# XWQ_Board1.net
KiCad netlist of a schematic drawn in EasyEDA Pro
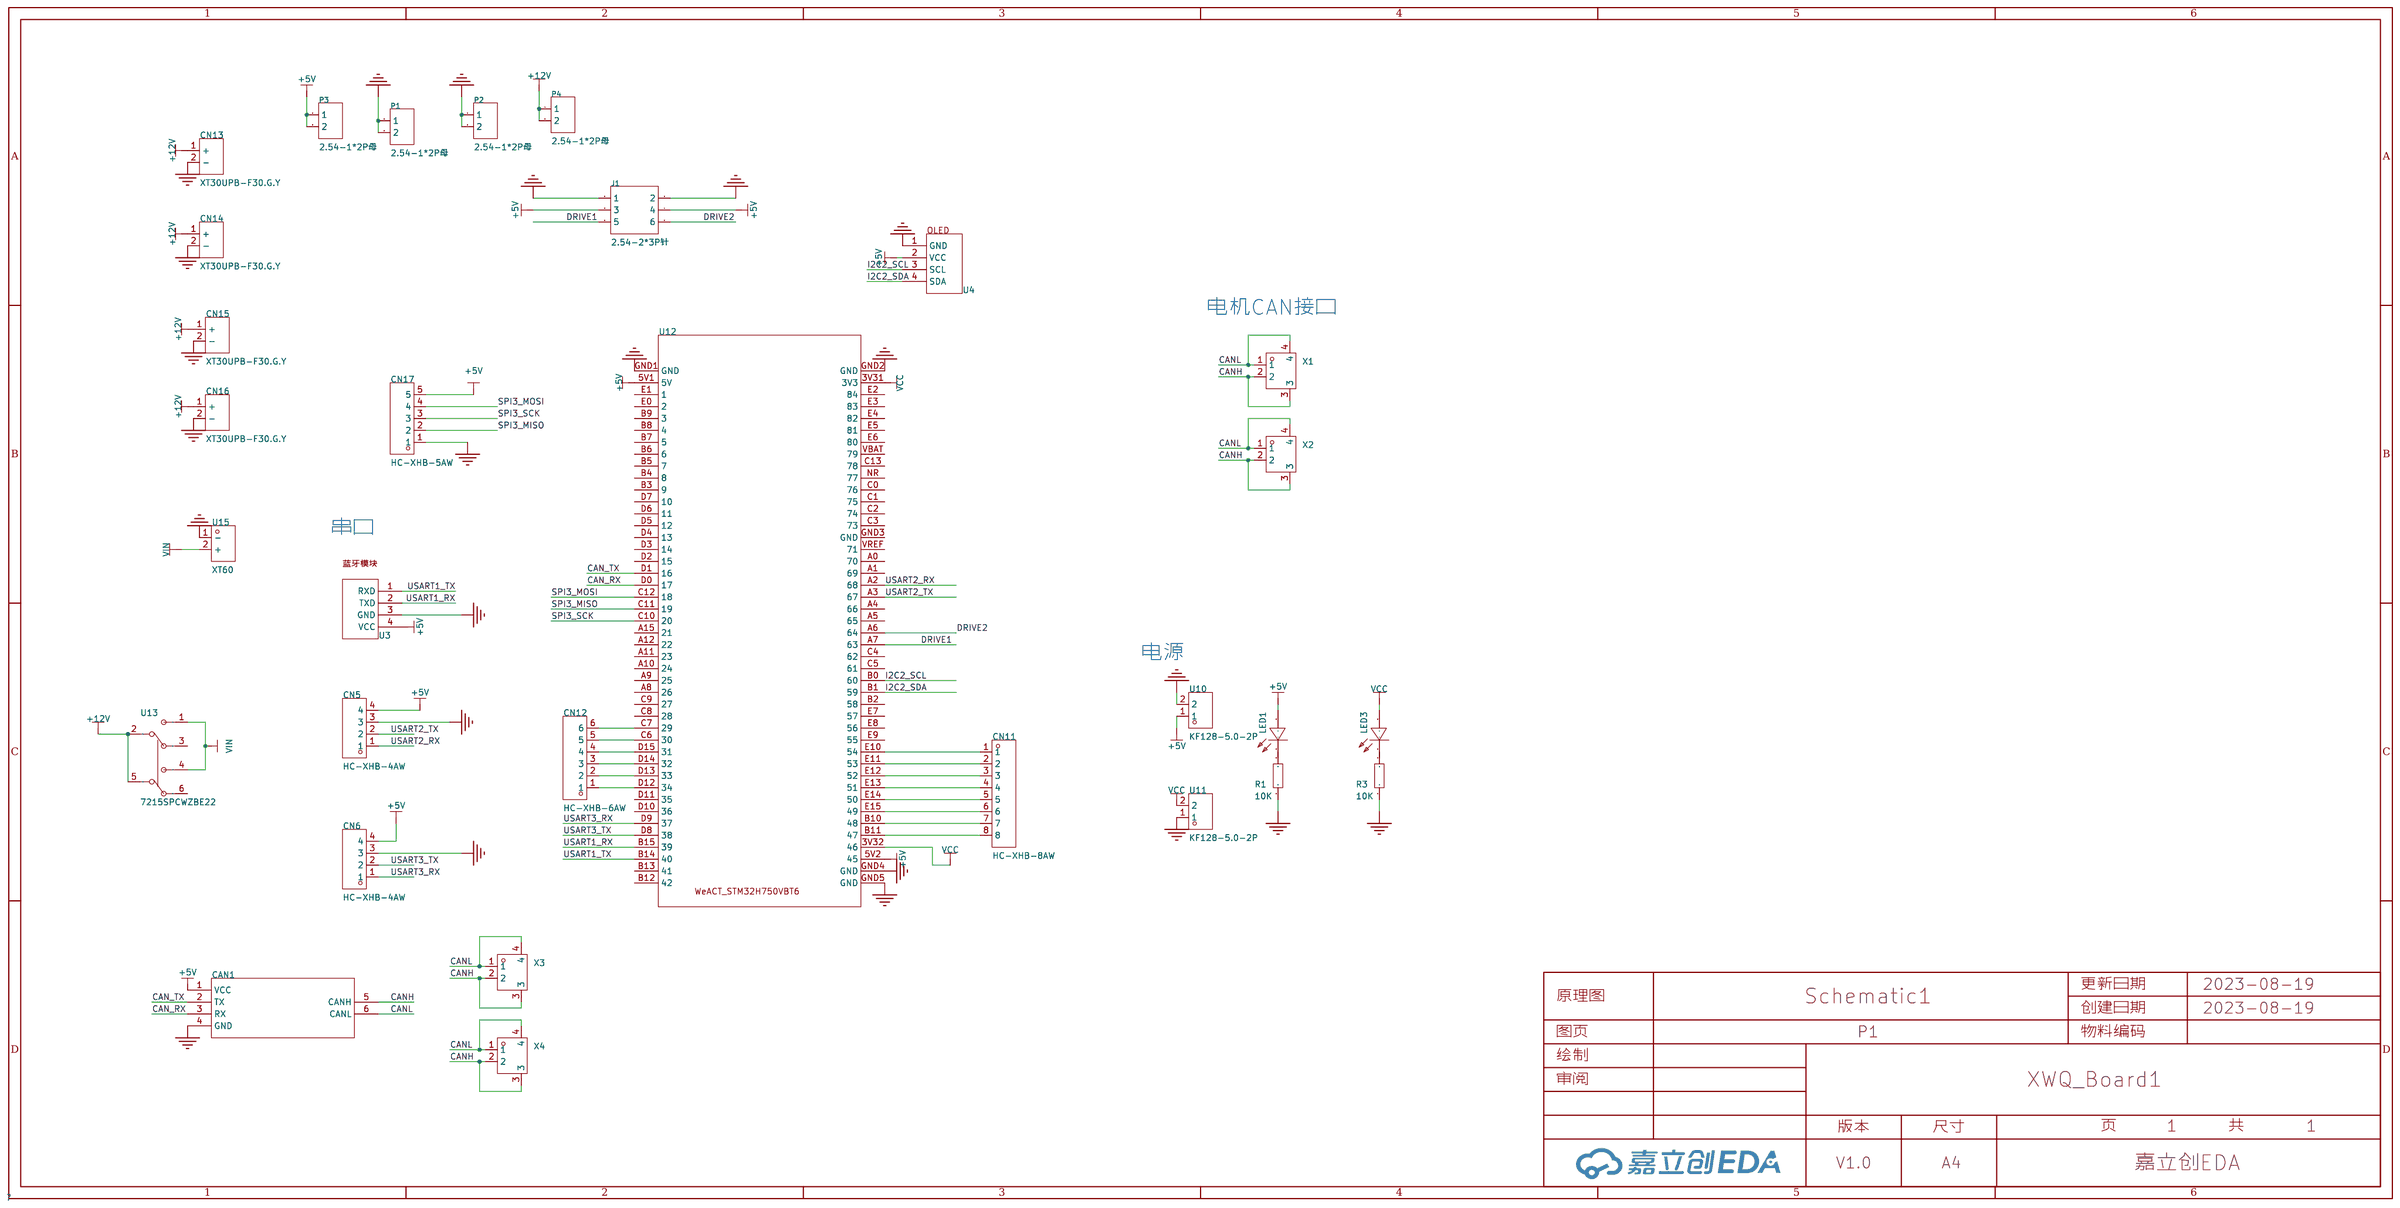
[diagram p0: schematic sheet]

(export (version "E")
  (design (tool "Eeschema 10.0.6"))
  (components
    (comp (ref "CAN1")
      (value "~")
      (footprint "easyedapro:CAN模块")
      (libsource (lib "easyedapro") (part "CAN模块"))
    )
    (comp (ref "CN5")
      (value "HC-XHB-4AW")
      (footprint "easyedapro:CONN-TH_4P-P2.5_HCTL_HC-XHB-4AW")
      (description "参考系列:-;间距:2.5mm;插针结构:1x4P;排数:1;每排PIN数:4;行距:-;公母:公型插针;安装方式:弯插;额定电流:3A;工作温度范围:-25°C~+85°C;")
      (fields (field (name "Manufacturer") "HCTL(华灿天禄)"))
      (libsource (lib "easyedapro") (part "HC-XHB-4AW"))
    )
    (comp (ref "CN6")
      (value "HC-XHB-4AW")
      (footprint "easyedapro:CONN-TH_4P-P2.5_HCTL_HC-XHB-4AW")
      (description "参考系列:-;间距:2.5mm;插针结构:1x4P;排数:1;每排PIN数:4;行距:-;公母:公型插针;安装方式:弯插;额定电流:3A;工作温度范围:-25°C~+85°C;")
      (fields (field (name "Manufacturer") "HCTL(华灿天禄)"))
      (libsource (lib "easyedapro") (part "HC-XHB-4AW"))
    )
    (comp (ref "CN11")
      (value "HC-XHB-8AW")
      (footprint "easyedapro:CONN-TH_HC-XHB-8AW")
      (description "参考系列:-;间距:2.5mm;插针结构:1x8P;排数:1;每排PIN数:8;行距:-;公母:公型插针;安装方式:弯插;额定电流:3A;工作温度范围:-25°C~+85°C;")
      (fields (field (name "Manufacturer") "HCTL(华灿天禄)"))
      (libsource (lib "easyedapro") (part "HC-XHB-8AW"))
    )
    (comp (ref "CN12")
      (value "HC-XHB-6AW")
      (footprint "easyedapro:CONN-TH_6P-P2.50_HCTL_HC-XHB-6AW")
      (description "参考系列:-;间距:2.5mm;插针结构:1x6P;排数:1;每排PIN数:6;行距:-;公母:公型插针;安装方式:弯插;额定电流:3A;工作温度范围:-25°C~+85°C;")
      (fields (field (name "Manufacturer") "HCTL(华灿天禄)"))
      (libsource (lib "easyedapro") (part "HC-XHB-6AW"))
    )
    (comp (ref "CN13")
      (value "XT30UPB-F30.G.Y")
      (footprint "easyedapro:CONN-TH_XT30UPB-F")
      (description "模型插头连接器")
      (fields (field (name "Manufacturer") "AMASS(艾迈斯)"))
      (libsource (lib "easyedapro") (part "XT30UPB-F"))
    )
    (comp (ref "CN14")
      (value "XT30UPB-F30.G.Y")
      (footprint "easyedapro:CONN-TH_XT30UPB-F")
      (description "模型插头连接器")
      (fields (field (name "Manufacturer") "AMASS(艾迈斯)"))
      (libsource (lib "easyedapro") (part "XT30UPB-F"))
    )
    (comp (ref "CN15")
      (value "XT30UPB-F30.G.Y")
      (footprint "easyedapro:CONN-TH_XT30UPB-F")
      (description "模型插头连接器")
      (fields (field (name "Manufacturer") "AMASS(艾迈斯)"))
      (libsource (lib "easyedapro") (part "XT30UPB-F"))
    )
    (comp (ref "CN16")
      (value "XT30UPB-F30.G.Y")
      (footprint "easyedapro:CONN-TH_XT30UPB-F")
      (description "模型插头连接器")
      (fields (field (name "Manufacturer") "AMASS(艾迈斯)"))
      (libsource (lib "easyedapro") (part "XT30UPB-F"))
    )
    (comp (ref "CN17")
      (value "HC-XHB-5AW")
      (footprint "easyedapro:CONN-TH_5P-P2.50_HCTL_HC-XHB-5AW")
      (description "参考系列:-;间距:2.5mm;插针结构:1x5P;排数:1;每排PIN数:5;行距:-;公母:公型插针;安装方式:弯插;额定电流:3A;工作温度范围:-25°C~+85°C;")
      (fields (field (name "Manufacturer") "HCTL(华灿天禄)"))
      (libsource (lib "easyedapro") (part "HC-XHB-5AW"))
    )
    (comp (ref "J1")
      (value "2.54-2*3P针")
      (footprint "easyedapro:HDR-TH_6P-P2.54-V-M-R2-C3-S2.54-1")
      (fields (field (name "Manufacturer") "BOOMELE(博穆精密)"))
      (libsource (lib "easyedapro") (part "Header-Male-2.54_2x3"))
    )
    (comp (ref "LED1")
      (value "NCD0805R1")
      (footprint "easyedapro:LED0805-RD_RED")
      (description "发光颜色:红灯;")
      (fields (field (name "Manufacturer") "国星光电"))
      (libsource (lib "easyedapro") (part "FC-2012HRK-620D"))
    )
    (comp (ref "LED3")
      (value "NCD0805R1")
      (footprint "easyedapro:LED0805-RD_RED")
      (description "发光颜色:红灯;")
      (fields (field (name "Manufacturer") "国星光电"))
      (libsource (lib "easyedapro") (part "FC-2012HRK-620D"))
    )
    (comp (ref "P1")
      (value "2.54-1*2P母")
      (footprint "easyedapro:HDR-TH_2P-P2.54-V-F")
      (description "排数:单排;总孔位数:2;间距:2.54mm;插孔结构:1x2P;行距:-;安装类型:直插;塑高:-;触头材质:-;触头镀层:-;")
      (fields (field (name "Manufacturer") "BOOMELE(博穆精密)"))
      (libsource (lib "easyedapro") (part "Header-Female-2.54_1x2"))
    )
    (comp (ref "P2")
      (value "2.54-1*2P母")
      (footprint "easyedapro:HDR-TH_2P-P2.54-V-F")
      (description "排数:单排;总孔位数:2;间距:2.54mm;插孔结构:1x2P;行距:-;安装类型:直插;塑高:-;触头材质:-;触头镀层:-;")
      (fields (field (name "Manufacturer") "BOOMELE(博穆精密)"))
      (libsource (lib "easyedapro") (part "Header-Female-2.54_1x2"))
    )
    (comp (ref "P3")
      (value "2.54-1*2P母")
      (footprint "easyedapro:HDR-TH_2P-P2.54-V-F")
      (description "排数:单排;总孔位数:2;间距:2.54mm;插孔结构:1x2P;行距:-;安装类型:直插;塑高:-;触头材质:-;触头镀层:-;")
      (fields (field (name "Manufacturer") "BOOMELE(博穆精密)"))
      (libsource (lib "easyedapro") (part "Header-Female-2.54_1x2"))
    )
    (comp (ref "P4")
      (value "2.54-1*2P母")
      (footprint "easyedapro:HDR-TH_2P-P2.54-V-F")
      (description "排数:单排;总孔位数:2;间距:2.54mm;插孔结构:1x2P;行距:-;安装类型:直插;塑高:-;触头材质:-;触头镀层:-;")
      (fields (field (name "Manufacturer") "BOOMELE(博穆精密)"))
      (libsource (lib "easyedapro") (part "Header-Female-2.54_1x2"))
    )
    (comp (ref "R1") (value "10K") (footprint "easyedapro:R0603") (libsource (lib "easyedapro") (part "电阻")))
    (comp (ref "R3") (value "10K") (footprint "easyedapro:R0603") (libsource (lib "easyedapro") (part "电阻")))
    (comp (ref "U3") (value "~") (footprint "easyedapro:蓝牙模块") (libsource (lib "easyedapro") (part "蓝牙模块")))
    (comp (ref "U4") (value "~") (footprint "easyedapro:OLED") (libsource (lib "easyedapro") (part "OLED")))
    (comp (ref "U10")
      (value "KF128-5.0-2P")
      (footprint "easyedapro:CONN-TH_P5.00_KF128-5.0-2P")
      (fields (field (name "Manufacturer") "KEFA(科发)"))
      (libsource (lib "easyedapro") (part "KF128-5.0-2P"))
    )
    (comp (ref "U11")
      (value "KF128-5.0-2P")
      (footprint "easyedapro:CONN-TH_P5.00_KF128-5.0-2P")
      (fields (field (name "Manufacturer") "KEFA(科发)"))
      (libsource (lib "easyedapro") (part "KF128-5.0-2P"))
    )
    (comp (ref "U12")
      (value "~")
      (footprint "easyedapro:WeAct_STM32H750VBT6核心板")
      (libsource (lib "easyedapro") (part "STM32H750VBT6"))
    )
    (comp (ref "U13")
      (value "7215SPCWZBE22")
      (footprint "easyedapro:SW-TH_6P-L12.7-W11.4-P4.70-LS4.8")
      (fields (field (name "Manufacturer") "CK"))
      (libsource (lib "easyedapro") (part "7215SPCWZBE22"))
    )
    (comp (ref "U15")
      (value "XT60")
      (footprint "easyedapro:CONN-TH_XT60")
      (description "模型锂电连接器 XT60-M")
      (fields (field (name "Manufacturer") "AMASS(艾迈斯)"))
      (libsource (lib "easyedapro") (part "XT60"))
    )
    (comp (ref "X1")
      (value "GH125-S02DCA-00")
      (footprint "easyedapro:CONN-SMD_2P-P1.25_JUSHUO_GH125-S02DCA-00")
      (description "参考系列:-;间距:1.25mm;插针结构:1x2P;排数:1;每排PIN数:2;行距:-;公母:公型插针;安装方式:卧贴;额定电流:1A;工作温度范围:-25°C~+85°C;")
      (fields (field (name "Manufacturer") "JS(钜硕电子)"))
      (libsource (lib "easyedapro") (part "GH125-S02DCA-00"))
    )
    (comp (ref "X2")
      (value "GH125-S02DCA-00")
      (footprint "easyedapro:CONN-SMD_2P-P1.25_JUSHUO_GH125-S02DCA-00")
      (description "参考系列:-;间距:1.25mm;插针结构:1x2P;排数:1;每排PIN数:2;行距:-;公母:公型插针;安装方式:卧贴;额定电流:1A;工作温度范围:-25°C~+85°C;")
      (fields (field (name "Manufacturer") "JS(钜硕电子)"))
      (libsource (lib "easyedapro") (part "GH125-S02DCA-00"))
    )
    (comp (ref "X3")
      (value "GH125-S02DCA-00")
      (footprint "easyedapro:CONN-SMD_2P-P1.25_JUSHUO_GH125-S02DCA-00")
      (description "参考系列:-;间距:1.25mm;插针结构:1x2P;排数:1;每排PIN数:2;行距:-;公母:公型插针;安装方式:卧贴;额定电流:1A;工作温度范围:-25°C~+85°C;")
      (fields (field (name "Manufacturer") "JS(钜硕电子)"))
      (libsource (lib "easyedapro") (part "GH125-S02DCA-00"))
    )
    (comp (ref "X4")
      (value "GH125-S02DCA-00")
      (footprint "easyedapro:CONN-SMD_2P-P1.25_JUSHUO_GH125-S02DCA-00")
      (description "参考系列:-;间距:1.25mm;插针结构:1x2P;排数:1;每排PIN数:2;行距:-;公母:公型插针;安装方式:卧贴;额定电流:1A;工作温度范围:-25°C~+85°C;")
      (fields (field (name "Manufacturer") "JS(钜硕电子)"))
      (libsource (lib "easyedapro") (part "GH125-S02DCA-00"))
    )
  )
  (nets
    (net (code "1") (name "+5V") (class "Default")
      (node (ref "CAN1") (pin "1") (pinfunction "VCC_1") (pintype "input"))
      (node (ref "CN17") (pin "5") (pinfunction "5_5") (pintype "input"))
      (node (ref "CN5") (pin "4") (pinfunction "4_4") (pintype "input"))
      (node (ref "CN6") (pin "4") (pinfunction "4_4") (pintype "input"))
      (node (ref "J1") (pin "3") (pinfunction "3_3") (pintype "input"))
      (node (ref "J1") (pin "4") (pinfunction "4_4") (pintype "input"))
      (node (ref "LED1") (pin "2") (pinfunction "+_2") (pintype "input"))
      (node (ref "P3") (pin "1") (pinfunction "1_1") (pintype "input"))
      (node (ref "P3") (pin "2") (pinfunction "2_2") (pintype "input"))
      (node (ref "U10") (pin "1") (pinfunction "1_1") (pintype "input"))
      (node (ref "U12") (pin "5V1") (pinfunction "5V_5V1") (pintype "input"))
      (node (ref "U12") (pin "5V2") (pinfunction "45_5V2") (pintype "input"))
      (node (ref "U3") (pin "4") (pinfunction "VCC_4") (pintype "input"))
      (node (ref "U4") (pin "2") (pinfunction "VCC_2") (pintype "input"))
    )
    (net (code "2") (name "+12V") (class "Default")
      (node (ref "CN13") (pin "1") (pinfunction "+_1") (pintype "input"))
      (node (ref "CN14") (pin "1") (pinfunction "+_1") (pintype "input"))
      (node (ref "CN15") (pin "1") (pinfunction "+_1") (pintype "input"))
      (node (ref "CN16") (pin "1") (pinfunction "+_1") (pintype "input"))
      (node (ref "P4") (pin "1") (pinfunction "1_1") (pintype "input"))
      (node (ref "P4") (pin "2") (pinfunction "2_2") (pintype "input"))
      (node (ref "U13") (pin "2") (pinfunction "2_2") (pintype "input"))
      (node (ref "U13") (pin "5") (pinfunction "5_5") (pintype "input"))
    )
    (net (code "3") (name "/CANH") (class "Default")
      (node (ref "CAN1") (pin "5") (pinfunction "CANH_5") (pintype "input"))
      (node (ref "X1") (pin "2") (pinfunction "2_2") (pintype "input"))
      (node (ref "X1") (pin "3") (pinfunction "3_3") (pintype "input"))
      (node (ref "X2") (pin "2") (pinfunction "2_2") (pintype "input"))
      (node (ref "X2") (pin "3") (pinfunction "3_3") (pintype "input"))
      (node (ref "X3") (pin "2") (pinfunction "2_2") (pintype "input"))
      (node (ref "X3") (pin "3") (pinfunction "3_3") (pintype "input"))
      (node (ref "X4") (pin "2") (pinfunction "2_2") (pintype "input"))
      (node (ref "X4") (pin "3") (pinfunction "3_3") (pintype "input"))
    )
    (net (code "4") (name "/CANL") (class "Default")
      (node (ref "CAN1") (pin "6") (pinfunction "CANL_6") (pintype "input"))
      (node (ref "X1") (pin "1") (pinfunction "1_1") (pintype "input"))
      (node (ref "X1") (pin "4") (pinfunction "4_4") (pintype "input"))
      (node (ref "X2") (pin "1") (pinfunction "1_1") (pintype "input"))
      (node (ref "X2") (pin "4") (pinfunction "4_4") (pintype "input"))
      (node (ref "X3") (pin "1") (pinfunction "1_1") (pintype "input"))
      (node (ref "X3") (pin "4") (pinfunction "4_4") (pintype "input"))
      (node (ref "X4") (pin "1") (pinfunction "1_1") (pintype "input"))
      (node (ref "X4") (pin "4") (pinfunction "4_4") (pintype "input"))
    )
    (net (code "5") (name "/CAN_RX") (class "Default")
      (node (ref "CAN1") (pin "3") (pinfunction "RX_3") (pintype "input"))
      (node (ref "U12") (pin "D0") (pinfunction "17_D0") (pintype "input"))
    )
    (net (code "6") (name "/CAN_TX") (class "Default")
      (node (ref "CAN1") (pin "2") (pinfunction "TX_2") (pintype "input"))
      (node (ref "U12") (pin "D1") (pinfunction "16_D1") (pintype "input"))
    )
    (net (code "7") (name "/DRIVE1") (class "Default")
      (node (ref "J1") (pin "5") (pinfunction "5_5") (pintype "input"))
      (node (ref "U12") (pin "A7") (pinfunction "63_A7") (pintype "input"))
    )
    (net (code "8") (name "/DRIVE2") (class "Default")
      (node (ref "J1") (pin "6") (pinfunction "6_6") (pintype "input"))
      (node (ref "U12") (pin "A6") (pinfunction "64_A6") (pintype "input"))
    )
    (net (code "9") (name "/I2C2_SCL") (class "Default")
      (node (ref "U12") (pin "B0") (pinfunction "60_B0") (pintype "input"))
      (node (ref "U4") (pin "3") (pinfunction "SCL_3") (pintype "input"))
    )
    (net (code "10") (name "/I2C2_SDA") (class "Default")
      (node (ref "U12") (pin "B1") (pinfunction "59_B1") (pintype "input"))
      (node (ref "U4") (pin "4") (pinfunction "SDA_4") (pintype "input"))
    )
    (net (code "11") (name "/SPI3_MISO") (class "Default")
      (node (ref "CN17") (pin "2") (pinfunction "2_2") (pintype "input"))
      (node (ref "U12") (pin "C11") (pinfunction "19_C11") (pintype "input"))
    )
    (net (code "12") (name "/SPI3_MOSI") (class "Default")
      (node (ref "CN17") (pin "4") (pinfunction "4_4") (pintype "input"))
      (node (ref "U12") (pin "C12") (pinfunction "18_C12") (pintype "input"))
    )
    (net (code "13") (name "/SPI3_SCK") (class "Default")
      (node (ref "CN17") (pin "3") (pinfunction "3_3") (pintype "input"))
      (node (ref "U12") (pin "C10") (pinfunction "20_C10") (pintype "input"))
    )
    (net (code "14") (name "/USART1_RX") (class "Default")
      (node (ref "U12") (pin "B15") (pinfunction "39_B15") (pintype "input"))
      (node (ref "U3") (pin "2") (pinfunction "TXD_2") (pintype "input"))
    )
    (net (code "15") (name "/USART1_TX") (class "Default")
      (node (ref "U12") (pin "B14") (pinfunction "40_B14") (pintype "input"))
      (node (ref "U3") (pin "1") (pinfunction "RXD_1") (pintype "input"))
    )
    (net (code "16") (name "/USART2_RX") (class "Default")
      (node (ref "CN5") (pin "1") (pinfunction "1_1") (pintype "input"))
      (node (ref "U12") (pin "A2") (pinfunction "68_A2") (pintype "input"))
    )
    (net (code "17") (name "/USART2_TX") (class "Default")
      (node (ref "CN5") (pin "2") (pinfunction "2_2") (pintype "input"))
      (node (ref "U12") (pin "A3") (pinfunction "67_A3") (pintype "input"))
    )
    (net (code "18") (name "/USART3_RX") (class "Default")
      (node (ref "CN6") (pin "1") (pinfunction "1_1") (pintype "input"))
      (node (ref "U12") (pin "D9") (pinfunction "37_D9") (pintype "input"))
    )
    (net (code "19") (name "/USART3_TX") (class "Default")
      (node (ref "CN6") (pin "2") (pinfunction "2_2") (pintype "input"))
      (node (ref "U12") (pin "D8") (pinfunction "38_D8") (pintype "input"))
    )
    (net (code "20") (name "GND") (class "Default")
      (node (ref "CAN1") (pin "4") (pinfunction "GND_4") (pintype "input"))
      (node (ref "CN13") (pin "2") (pinfunction "-_2") (pintype "input"))
      (node (ref "CN14") (pin "2") (pinfunction "-_2") (pintype "input"))
      (node (ref "CN15") (pin "2") (pinfunction "-_2") (pintype "input"))
      (node (ref "CN16") (pin "2") (pinfunction "-_2") (pintype "input"))
      (node (ref "CN17") (pin "1") (pinfunction "1_1") (pintype "input"))
      (node (ref "CN5") (pin "3") (pinfunction "3_3") (pintype "input"))
      (node (ref "CN6") (pin "3") (pinfunction "3_3") (pintype "input"))
      (node (ref "J1") (pin "1") (pinfunction "1_1") (pintype "input"))
      (node (ref "J1") (pin "2") (pinfunction "2_2") (pintype "input"))
      (node (ref "P1") (pin "1") (pinfunction "1_1") (pintype "input"))
      (node (ref "P1") (pin "2") (pinfunction "2_2") (pintype "input"))
      (node (ref "P2") (pin "1") (pinfunction "1_1") (pintype "input"))
      (node (ref "P2") (pin "2") (pinfunction "2_2") (pintype "input"))
      (node (ref "R1") (pin "1") (pinfunction "1_1") (pintype "input"))
      (node (ref "R3") (pin "1") (pinfunction "1_1") (pintype "input"))
      (node (ref "U10") (pin "2") (pinfunction "2_2") (pintype "input"))
      (node (ref "U11") (pin "1") (pinfunction "1_1") (pintype "input"))
      (node (ref "U12") (pin "GND1") (pinfunction "GND_GND1") (pintype "input"))
      (node (ref "U12") (pin "GND2") (pinfunction "GND_GND2") (pintype "input"))
      (node (ref "U12") (pin "GND4") (pinfunction "GND_GND4") (pintype "input"))
      (node (ref "U12") (pin "GND5") (pinfunction "GND_GND5") (pintype "input"))
      (node (ref "U15") (pin "1") (pinfunction "-_1") (pintype "input"))
      (node (ref "U3") (pin "3") (pinfunction "GND_3") (pintype "input"))
      (node (ref "U4") (pin "1") (pinfunction "GND_1") (pintype "input"))
    )
    (net (code "21") (name "Net-(LED1--)") (class "Default")
      (node (ref "LED1") (pin "1") (pinfunction "-_1") (pintype "input"))
      (node (ref "R1") (pin "2") (pinfunction "2_2") (pintype "input"))
    )
    (net (code "22") (name "Net-(LED3--)") (class "Default")
      (node (ref "LED3") (pin "1") (pinfunction "-_1") (pintype "input"))
      (node (ref "R3") (pin "2") (pinfunction "2_2") (pintype "input"))
    )
    (net (code "23") (name "Net-(U12-29)") (class "Default")
      (node (ref "CN12") (pin "6") (pinfunction "6_6") (pintype "input"))
      (node (ref "U12") (pin "C7") (pinfunction "29_C7") (pintype "input"))
    )
    (net (code "24") (name "Net-(U12-30)") (class "Default")
      (node (ref "CN12") (pin "5") (pinfunction "5_5") (pintype "input"))
      (node (ref "U12") (pin "C6") (pinfunction "30_C6") (pintype "input"))
    )
    (net (code "25") (name "Net-(U12-31)") (class "Default")
      (node (ref "CN12") (pin "4") (pinfunction "4_4") (pintype "input"))
      (node (ref "U12") (pin "D15") (pinfunction "31_D15") (pintype "input"))
    )
    (net (code "26") (name "Net-(U12-32)") (class "Default")
      (node (ref "CN12") (pin "3") (pinfunction "3_3") (pintype "input"))
      (node (ref "U12") (pin "D14") (pinfunction "32_D14") (pintype "input"))
    )
    (net (code "27") (name "Net-(U12-33)") (class "Default")
      (node (ref "CN12") (pin "2") (pinfunction "2_2") (pintype "input"))
      (node (ref "U12") (pin "D13") (pinfunction "33_D13") (pintype "input"))
    )
    (net (code "28") (name "Net-(U12-34)") (class "Default")
      (node (ref "CN12") (pin "1") (pinfunction "1_1") (pintype "input"))
      (node (ref "U12") (pin "D12") (pinfunction "34_D12") (pintype "input"))
    )
    (net (code "29") (name "Net-(U12-47)") (class "Default")
      (node (ref "CN11") (pin "8") (pinfunction "8_8") (pintype "input"))
      (node (ref "U12") (pin "B11") (pinfunction "47_B11") (pintype "input"))
    )
    (net (code "30") (name "Net-(U12-48)") (class "Default")
      (node (ref "CN11") (pin "7") (pinfunction "7_7") (pintype "input"))
      (node (ref "U12") (pin "B10") (pinfunction "48_B10") (pintype "input"))
    )
    (net (code "31") (name "Net-(U12-49)") (class "Default")
      (node (ref "CN11") (pin "6") (pinfunction "6_6") (pintype "input"))
      (node (ref "U12") (pin "E15") (pinfunction "49_E15") (pintype "input"))
    )
    (net (code "32") (name "Net-(U12-50)") (class "Default")
      (node (ref "CN11") (pin "5") (pinfunction "5_5") (pintype "input"))
      (node (ref "U12") (pin "E14") (pinfunction "50_E14") (pintype "input"))
    )
    (net (code "33") (name "Net-(U12-51)") (class "Default")
      (node (ref "CN11") (pin "4") (pinfunction "4_4") (pintype "input"))
      (node (ref "U12") (pin "E13") (pinfunction "51_E13") (pintype "input"))
    )
    (net (code "34") (name "Net-(U12-52)") (class "Default")
      (node (ref "CN11") (pin "3") (pinfunction "3_3") (pintype "input"))
      (node (ref "U12") (pin "E12") (pinfunction "52_E12") (pintype "input"))
    )
    (net (code "35") (name "Net-(U12-53)") (class "Default")
      (node (ref "CN11") (pin "2") (pinfunction "2_2") (pintype "input"))
      (node (ref "U12") (pin "E11") (pinfunction "53_E11") (pintype "input"))
    )
    (net (code "36") (name "Net-(U12-54)") (class "Default")
      (node (ref "CN11") (pin "1") (pinfunction "1_1") (pintype "input"))
      (node (ref "U12") (pin "E10") (pinfunction "54_E10") (pintype "input"))
    )
    (net (code "37") (name "VCC") (class "Default")
      (node (ref "LED3") (pin "2") (pinfunction "+_2") (pintype "input"))
      (node (ref "U11") (pin "2") (pinfunction "2_2") (pintype "input"))
      (node (ref "U12") (pin "3V31") (pinfunction "3V3_3V31") (pintype "input"))
      (node (ref "U12") (pin "3V32") (pinfunction "46_3V32") (pintype "input"))
    )
    (net (code "38") (name "VIN") (class "Default")
      (node (ref "U13") (pin "1") (pinfunction "1_1") (pintype "input"))
      (node (ref "U13") (pin "4") (pinfunction "4_4") (pintype "input"))
      (node (ref "U15") (pin "2") (pinfunction "+_2") (pintype "input"))
    )
    (net (code "39") (name "unconnected-(U12-1-PadE1)") (class "Default")
      (node (ref "U12") (pin "E1") (pinfunction "1_E1") (pintype "input"))
    )
    (net (code "40") (name "unconnected-(U12-2-PadE0)") (class "Default")
      (node (ref "U12") (pin "E0") (pinfunction "2_E0") (pintype "input"))
    )
    (net (code "41") (name "unconnected-(U12-3-PadB9)") (class "Default")
      (node (ref "U12") (pin "B9") (pinfunction "3_B9") (pintype "input"))
    )
    (net (code "42") (name "unconnected-(U12-4-PadB8)") (class "Default")
      (node (ref "U12") (pin "B8") (pinfunction "4_B8") (pintype "input"))
    )
    (net (code "43") (name "unconnected-(U12-5-PadB7)") (class "Default")
      (node (ref "U12") (pin "B7") (pinfunction "5_B7") (pintype "input"))
    )
    (net (code "44") (name "unconnected-(U12-6-PadB6)") (class "Default")
      (node (ref "U12") (pin "B6") (pinfunction "6_B6") (pintype "input"))
    )
    (net (code "45") (name "unconnected-(U12-7-PadB5)") (class "Default")
      (node (ref "U12") (pin "B5") (pinfunction "7_B5") (pintype "input"))
    )
    (net (code "46") (name "unconnected-(U12-8-PadB4)") (class "Default")
      (node (ref "U12") (pin "B4") (pinfunction "8_B4") (pintype "input"))
    )
    (net (code "47") (name "unconnected-(U12-9-PadB3)") (class "Default")
      (node (ref "U12") (pin "B3") (pinfunction "9_B3") (pintype "input"))
    )
    (net (code "48") (name "unconnected-(U12-10-PadD7)") (class "Default")
      (node (ref "U12") (pin "D7") (pinfunction "10_D7") (pintype "input"))
    )
    (net (code "49") (name "unconnected-(U12-11-PadD6)") (class "Default")
      (node (ref "U12") (pin "D6") (pinfunction "11_D6") (pintype "input"))
    )
    (net (code "50") (name "unconnected-(U12-12-PadD5)") (class "Default")
      (node (ref "U12") (pin "D5") (pinfunction "12_D5") (pintype "input"))
    )
    (net (code "51") (name "unconnected-(U12-13-PadD4)") (class "Default")
      (node (ref "U12") (pin "D4") (pinfunction "13_D4") (pintype "input"))
    )
    (net (code "52") (name "unconnected-(U12-14-PadD3)") (class "Default")
      (node (ref "U12") (pin "D3") (pinfunction "14_D3") (pintype "input"))
    )
    (net (code "53") (name "unconnected-(U12-15-PadD2)") (class "Default")
      (node (ref "U12") (pin "D2") (pinfunction "15_D2") (pintype "input"))
    )
    (net (code "54") (name "unconnected-(U12-21-PadA15)") (class "Default")
      (node (ref "U12") (pin "A15") (pinfunction "21_A15") (pintype "input"))
    )
    (net (code "55") (name "unconnected-(U12-22-PadA12)") (class "Default")
      (node (ref "U12") (pin "A12") (pinfunction "22_A12") (pintype "input"))
    )
    (net (code "56") (name "unconnected-(U12-23-PadA11)") (class "Default")
      (node (ref "U12") (pin "A11") (pinfunction "23_A11") (pintype "input"))
    )
    (net (code "57") (name "unconnected-(U12-24-PadA10)") (class "Default")
      (node (ref "U12") (pin "A10") (pinfunction "24_A10") (pintype "input"))
    )
    (net (code "58") (name "unconnected-(U12-25-PadA9)") (class "Default")
      (node (ref "U12") (pin "A9") (pinfunction "25_A9") (pintype "input"))
    )
    (net (code "59") (name "unconnected-(U12-26-PadA8)") (class "Default")
      (node (ref "U12") (pin "A8") (pinfunction "26_A8") (pintype "input"))
    )
    (net (code "60") (name "unconnected-(U12-27-PadC9)") (class "Default")
      (node (ref "U12") (pin "C9") (pinfunction "27_C9") (pintype "input"))
    )
    (net (code "61") (name "unconnected-(U12-28-PadC8)") (class "Default")
      (node (ref "U12") (pin "C8") (pinfunction "28_C8") (pintype "input"))
    )
    (net (code "62") (name "unconnected-(U12-35-PadD11)") (class "Default")
      (node (ref "U12") (pin "D11") (pinfunction "35_D11") (pintype "input"))
    )
    (net (code "63") (name "unconnected-(U12-36-PadD10)") (class "Default")
      (node (ref "U12") (pin "D10") (pinfunction "36_D10") (pintype "input"))
    )
    (net (code "64") (name "unconnected-(U12-41-PadB13)") (class "Default")
      (node (ref "U12") (pin "B13") (pinfunction "41_B13") (pintype "input"))
    )
    (net (code "65") (name "unconnected-(U12-42-PadB12)") (class "Default")
      (node (ref "U12") (pin "B12") (pinfunction "42_B12") (pintype "input"))
    )
    (net (code "66") (name "unconnected-(U12-55-PadE9)") (class "Default")
      (node (ref "U12") (pin "E9") (pinfunction "55_E9") (pintype "input"))
    )
    (net (code "67") (name "unconnected-(U12-56-PadE8)") (class "Default")
      (node (ref "U12") (pin "E8") (pinfunction "56_E8") (pintype "input"))
    )
    (net (code "68") (name "unconnected-(U12-57-PadE7)") (class "Default")
      (node (ref "U12") (pin "E7") (pinfunction "57_E7") (pintype "input"))
    )
    (net (code "69") (name "unconnected-(U12-58-PadB2)") (class "Default")
      (node (ref "U12") (pin "B2") (pinfunction "58_B2") (pintype "input"))
    )
    (net (code "70") (name "unconnected-(U12-61-PadC5)") (class "Default")
      (node (ref "U12") (pin "C5") (pinfunction "61_C5") (pintype "input"))
    )
    (net (code "71") (name "unconnected-(U12-62-PadC4)") (class "Default")
      (node (ref "U12") (pin "C4") (pinfunction "62_C4") (pintype "input"))
    )
    (net (code "72") (name "unconnected-(U12-65-PadA5)") (class "Default")
      (node (ref "U12") (pin "A5") (pinfunction "65_A5") (pintype "input"))
    )
    (net (code "73") (name "unconnected-(U12-66-PadA4)") (class "Default")
      (node (ref "U12") (pin "A4") (pinfunction "66_A4") (pintype "input"))
    )
    (net (code "74") (name "unconnected-(U12-69-PadA1)") (class "Default")
      (node (ref "U12") (pin "A1") (pinfunction "69_A1") (pintype "input"))
    )
    (net (code "75") (name "unconnected-(U12-70-PadA0)") (class "Default")
      (node (ref "U12") (pin "A0") (pinfunction "70_A0") (pintype "input"))
    )
    (net (code "76") (name "unconnected-(U12-71-PadVREF)") (class "Default")
      (node (ref "U12") (pin "VREF") (pinfunction "71_VREF") (pintype "input"))
    )
    (net (code "77") (name "unconnected-(U12-73-PadC3)") (class "Default")
      (node (ref "U12") (pin "C3") (pinfunction "73_C3") (pintype "input"))
    )
    (net (code "78") (name "unconnected-(U12-74-PadC2)") (class "Default")
      (node (ref "U12") (pin "C2") (pinfunction "74_C2") (pintype "input"))
    )
    (net (code "79") (name "unconnected-(U12-75-PadC1)") (class "Default")
      (node (ref "U12") (pin "C1") (pinfunction "75_C1") (pintype "input"))
    )
    (net (code "80") (name "unconnected-(U12-76-PadC0)") (class "Default")
      (node (ref "U12") (pin "C0") (pinfunction "76_C0") (pintype "input"))
    )
    (net (code "81") (name "unconnected-(U12-77-PadNR)") (class "Default")
      (node (ref "U12") (pin "NR") (pinfunction "77_NR") (pintype "input"))
    )
    (net (code "82") (name "unconnected-(U12-78-PadC13)") (class "Default")
      (node (ref "U12") (pin "C13") (pinfunction "78_C13") (pintype "input"))
    )
    (net (code "83") (name "unconnected-(U12-79-PadVBAT)") (class "Default")
      (node (ref "U12") (pin "VBAT") (pinfunction "79_VBAT") (pintype "input"))
    )
    (net (code "84") (name "unconnected-(U12-80-PadE6)") (class "Default")
      (node (ref "U12") (pin "E6") (pinfunction "80_E6") (pintype "input"))
    )
    (net (code "85") (name "unconnected-(U12-81-PadE5)") (class "Default")
      (node (ref "U12") (pin "E5") (pinfunction "81_E5") (pintype "input"))
    )
    (net (code "86") (name "unconnected-(U12-82-PadE4)") (class "Default")
      (node (ref "U12") (pin "E4") (pinfunction "82_E4") (pintype "input"))
    )
    (net (code "87") (name "unconnected-(U12-83-PadE3)") (class "Default")
      (node (ref "U12") (pin "E3") (pinfunction "83_E3") (pintype "input"))
    )
    (net (code "88") (name "unconnected-(U12-84-PadE2)") (class "Default")
      (node (ref "U12") (pin "E2") (pinfunction "84_E2") (pintype "input"))
    )
    (net (code "89") (name "unconnected-(U12-GND-PadGND3)") (class "Default")
      (node (ref "U12") (pin "GND3") (pinfunction "GND_GND3") (pintype "input"))
    )
    (net (code "90") (name "unconnected-(U13-Pad3)") (class "Default")
      (node (ref "U13") (pin "3") (pinfunction "3_3") (pintype "input"))
    )
    (net (code "91") (name "unconnected-(U13-Pad6)") (class "Default")
      (node (ref "U13") (pin "6") (pinfunction "6_6") (pintype "input"))
    )
  )
)
